# fm_mod_fpga.net
KiCad netlist of a schematic drawn in EAGLE
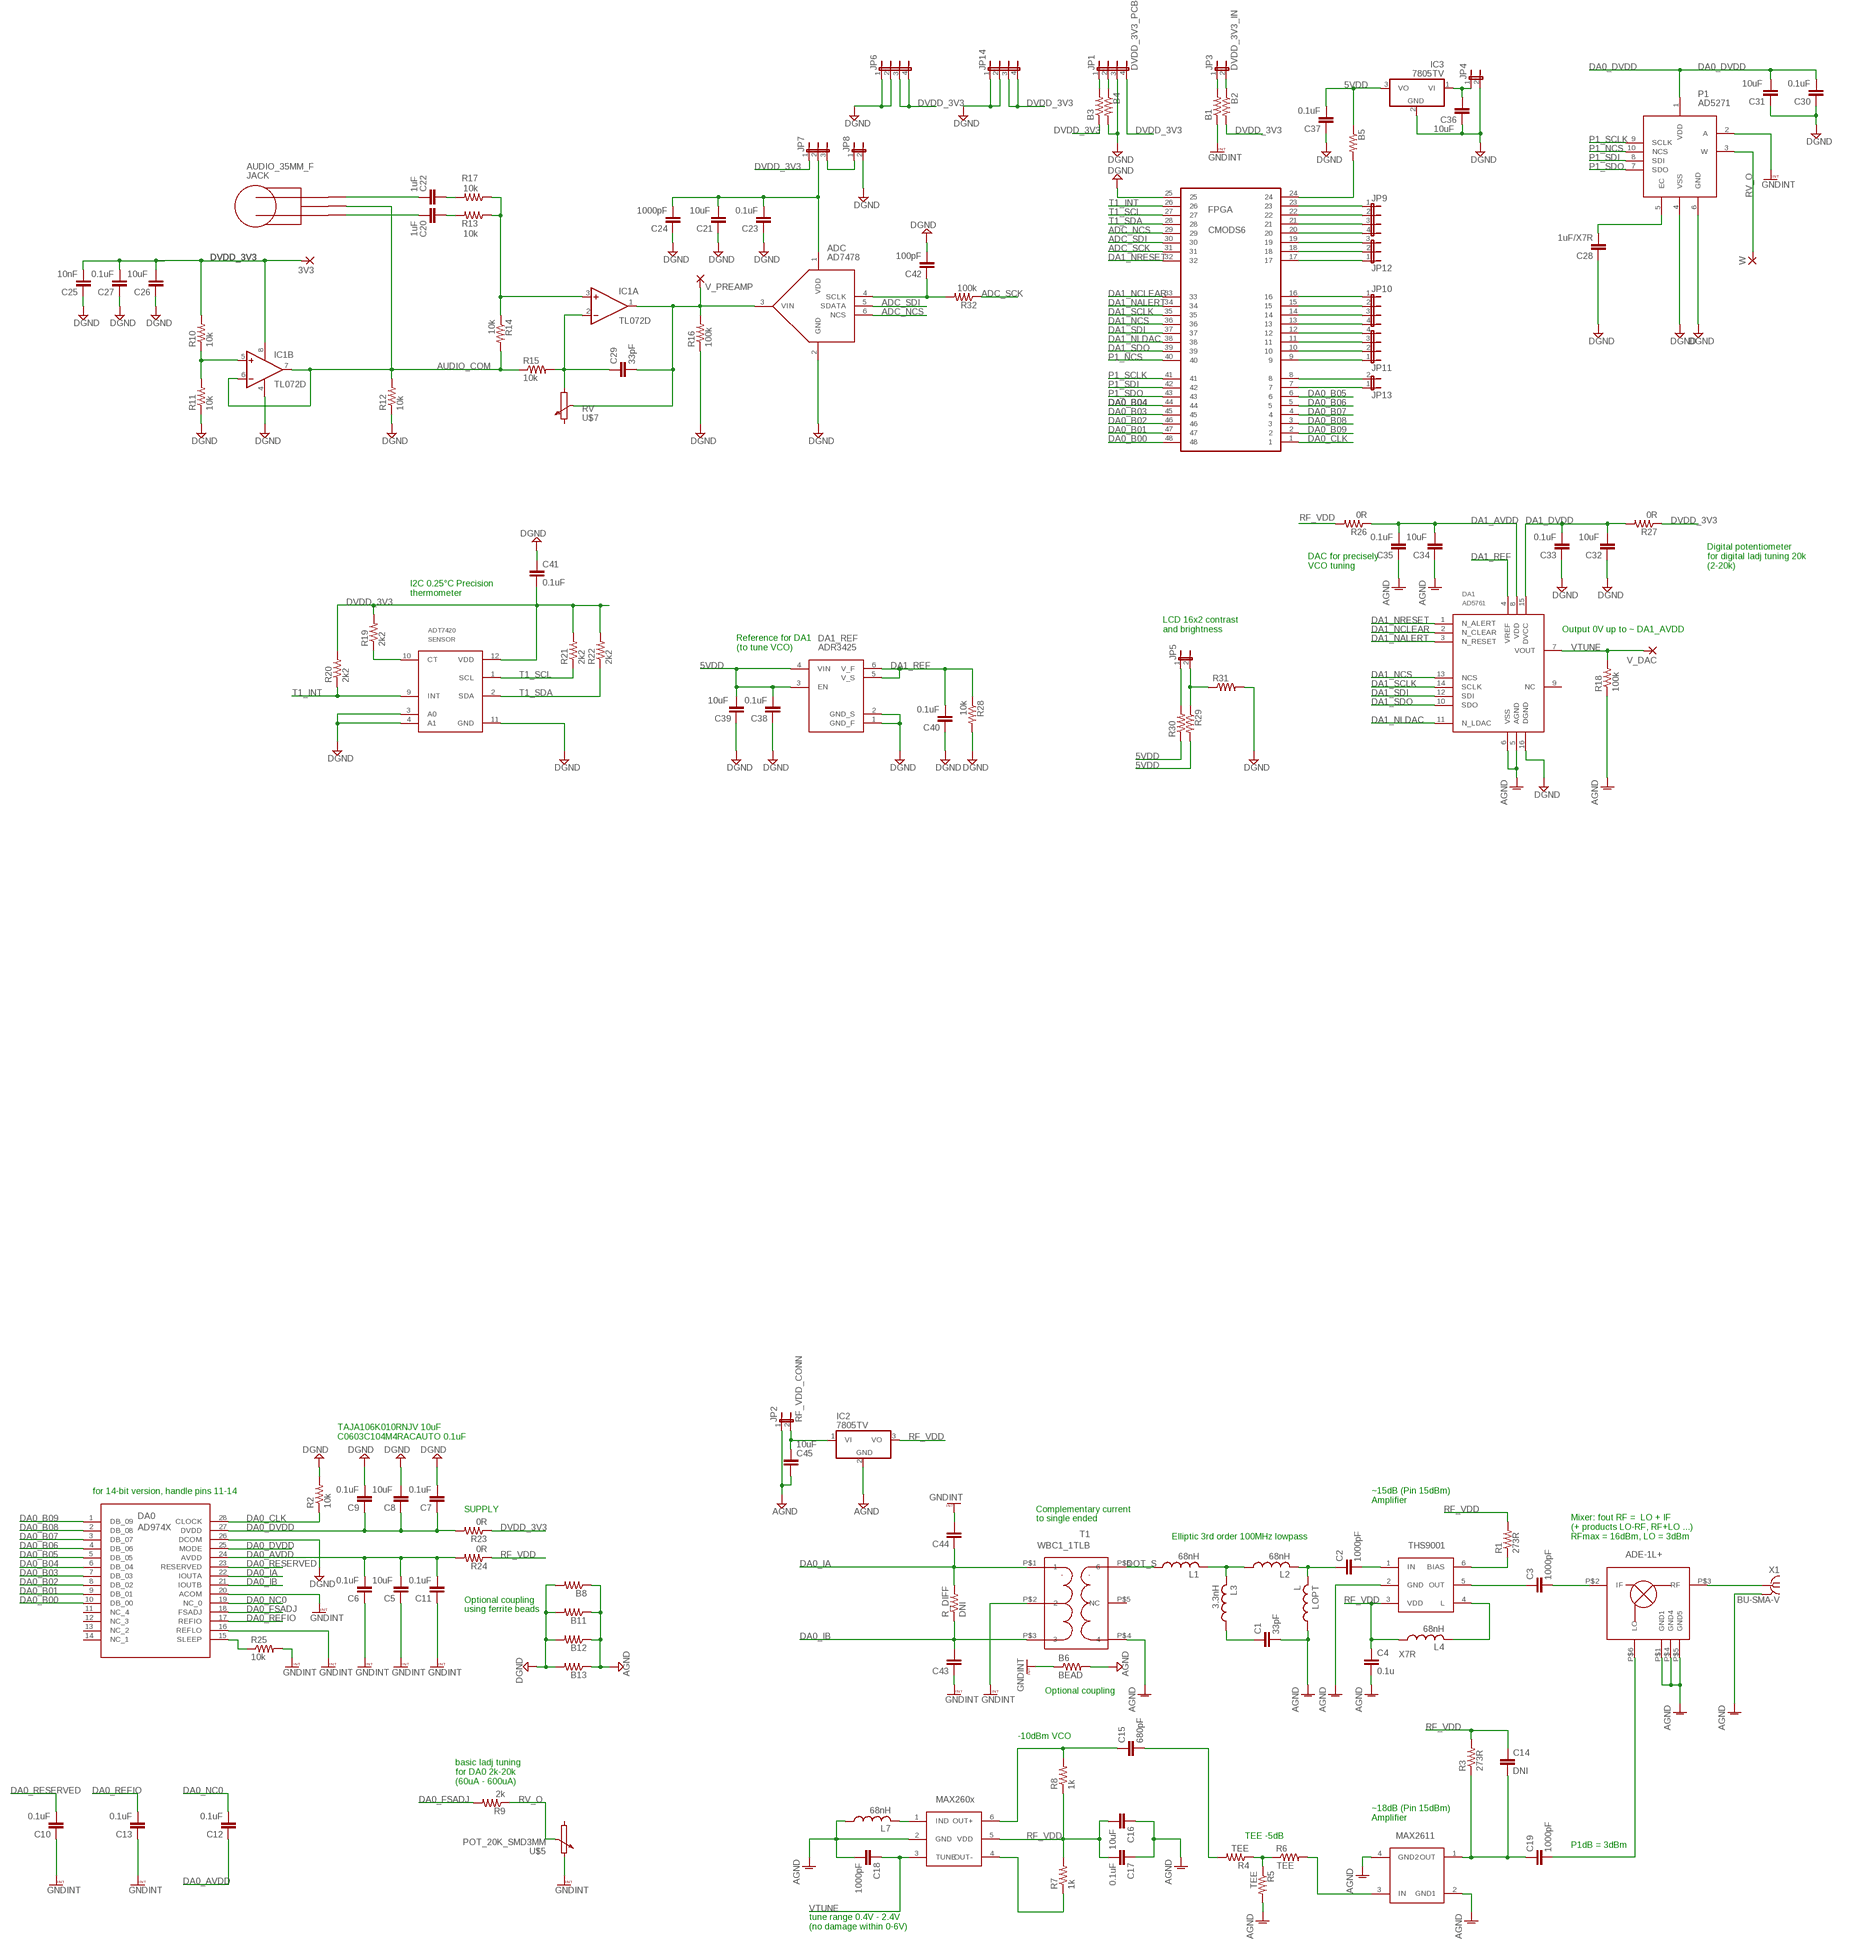
[diagram p0: schematic, sheet 1]

(export (version "E")
  (design (tool "Eeschema 10.0.6"))
  (components
    (comp (ref "3V3")
      (value "WIREPAD1,6/0,8")
      (footprint "eagle-import:1,6_0,8")
      (libsource (lib "eagle-import") (part "WIREPAD1,6/0,8"))
    )
    (comp (ref "ADC")
      (value "AD7478")
      (footprint "eagle-import:SOT23-6")
      (libsource (lib "eagle-import") (part "AD7478"))
    )
    (comp (ref "B1")
      (value "R-US_M0805")
      (footprint "eagle-import:M0805")
      (libsource (lib "eagle-import") (part "resistor_R-US_M0805"))
    )
    (comp (ref "B2")
      (value "R-US_M0805")
      (footprint "eagle-import:M0805")
      (libsource (lib "eagle-import") (part "resistor_R-US_M0805"))
    )
    (comp (ref "B3")
      (value "R-US_M0805")
      (footprint "eagle-import:M0805")
      (libsource (lib "eagle-import") (part "resistor_R-US_M0805"))
    )
    (comp (ref "B4")
      (value "R-US_M0805")
      (footprint "eagle-import:M0805")
      (libsource (lib "eagle-import") (part "resistor_R-US_M0805"))
    )
    (comp (ref "B5")
      (value "R-US_M0805")
      (footprint "eagle-import:M0805")
      (libsource (lib "eagle-import") (part "resistor_R-US_M0805"))
    )
    (comp (ref "B6")
      (value "BEAD")
      (footprint "eagle-import:M0805")
      (libsource (lib "eagle-import") (part "resistor_R-US_M0805"))
    )
    (comp (ref "B8")
      (value "R-US_M0805")
      (footprint "eagle-import:M0805")
      (libsource (lib "eagle-import") (part "resistor_R-US_M0805"))
    )
    (comp (ref "B11")
      (value "R-US_M0805")
      (footprint "eagle-import:M0805")
      (libsource (lib "eagle-import") (part "resistor_R-US_M0805"))
    )
    (comp (ref "B12")
      (value "R-US_M0805")
      (footprint "eagle-import:M0805")
      (libsource (lib "eagle-import") (part "resistor_R-US_M0805"))
    )
    (comp (ref "B13")
      (value "R-US_M0805")
      (footprint "eagle-import:M0805")
      (libsource (lib "eagle-import") (part "resistor_R-US_M0805"))
    )
    (comp (ref "C1")
      (value "33pF")
      (footprint "eagle-import:C0603")
      (libsource (lib "eagle-import") (part "C-EUC0603"))
    )
    (comp (ref "C2")
      (value "1000pF")
      (footprint "eagle-import:C0805")
      (libsource (lib "eagle-import") (part "C-EUC0805"))
    )
    (comp (ref "C3")
      (value "1000pF")
      (footprint "eagle-import:C0805")
      (libsource (lib "eagle-import") (part "C-EUC0805"))
    )
    (comp (ref "C4")
      (value "0.1u")
      (footprint "eagle-import:C0805")
      (libsource (lib "eagle-import") (part "C-EUC0805"))
    )
    (comp (ref "C5")
      (value "10uF")
      (footprint "eagle-import:C1206")
      (libsource (lib "eagle-import") (part "C-EUC1206"))
    )
    (comp (ref "C6")
      (value "0.1uF")
      (footprint "eagle-import:C0603")
      (libsource (lib "eagle-import") (part "C-EUC0603"))
    )
    (comp (ref "C7")
      (value "0.1uF")
      (footprint "eagle-import:C0603")
      (libsource (lib "eagle-import") (part "C-EUC0603"))
    )
    (comp (ref "C8")
      (value "10uF")
      (footprint "eagle-import:C1206")
      (libsource (lib "eagle-import") (part "C-EUC1206"))
    )
    (comp (ref "C9")
      (value "0.1uF")
      (footprint "eagle-import:C0603")
      (libsource (lib "eagle-import") (part "C-EUC0603"))
    )
    (comp (ref "C10")
      (value "0.1uF")
      (footprint "eagle-import:C0603")
      (libsource (lib "eagle-import") (part "C-EUC0603"))
    )
    (comp (ref "C11")
      (value "0.1uF")
      (footprint "eagle-import:C0603")
      (libsource (lib "eagle-import") (part "C-EUC0603"))
    )
    (comp (ref "C12")
      (value "0.1uF")
      (footprint "eagle-import:C0603")
      (libsource (lib "eagle-import") (part "C-EUC0603"))
    )
    (comp (ref "C13")
      (value "0.1uF")
      (footprint "eagle-import:C0603")
      (libsource (lib "eagle-import") (part "C-EUC0603"))
    )
    (comp (ref "C14")
      (value "DNI")
      (footprint "eagle-import:C0603")
      (libsource (lib "eagle-import") (part "C-EUC0603"))
    )
    (comp (ref "C15")
      (value "680pF")
      (footprint "eagle-import:C0805")
      (libsource (lib "eagle-import") (part "C-EUC0805"))
    )
    (comp (ref "C16")
      (value "10uF")
      (footprint "eagle-import:C1206")
      (libsource (lib "eagle-import") (part "C-EUC1206"))
    )
    (comp (ref "C17")
      (value "0.1uF")
      (footprint "eagle-import:C0603")
      (libsource (lib "eagle-import") (part "C-EUC0603"))
    )
    (comp (ref "C18")
      (value "1000pF")
      (footprint "eagle-import:C0805")
      (libsource (lib "eagle-import") (part "C-EUC0805"))
    )
    (comp (ref "C19")
      (value "1000pF")
      (footprint "eagle-import:C0805")
      (libsource (lib "eagle-import") (part "C-EUC0805"))
    )
    (comp (ref "C20")
      (value "1uF")
      (footprint "eagle-import:C1206")
      (libsource (lib "eagle-import") (part "C-EUC1206"))
    )
    (comp (ref "C21")
      (value "10uF")
      (footprint "eagle-import:C1206")
      (libsource (lib "eagle-import") (part "C-EUC1206"))
    )
    (comp (ref "C22")
      (value "1uF")
      (footprint "eagle-import:C1206")
      (libsource (lib "eagle-import") (part "C-EUC1206"))
    )
    (comp (ref "C23")
      (value "0.1uF")
      (footprint "eagle-import:C0603")
      (libsource (lib "eagle-import") (part "C-EUC0603"))
    )
    (comp (ref "C24")
      (value "1000pF")
      (footprint "eagle-import:C0805")
      (libsource (lib "eagle-import") (part "C-EUC0805"))
    )
    (comp (ref "C25")
      (value "10nF")
      (footprint "eagle-import:C0805")
      (libsource (lib "eagle-import") (part "C-EUC0805"))
    )
    (comp (ref "C26")
      (value "10uF")
      (footprint "eagle-import:C1206")
      (libsource (lib "eagle-import") (part "C-EUC1206"))
    )
    (comp (ref "C27")
      (value "0.1uF")
      (footprint "eagle-import:C0603")
      (libsource (lib "eagle-import") (part "C-EUC0603"))
    )
    (comp (ref "C28")
      (value "1uF/X7R")
      (footprint "eagle-import:C0805")
      (libsource (lib "eagle-import") (part "C-EUC0805"))
    )
    (comp (ref "C29")
      (value "33pF")
      (footprint "eagle-import:C0603")
      (libsource (lib "eagle-import") (part "C-EUC0603"))
    )
    (comp (ref "C30")
      (value "0.1uF")
      (footprint "eagle-import:C0603")
      (libsource (lib "eagle-import") (part "C-EUC0603"))
    )
    (comp (ref "C31")
      (value "10uF")
      (footprint "eagle-import:C1206")
      (libsource (lib "eagle-import") (part "C-EUC1206"))
    )
    (comp (ref "C32")
      (value "10uF")
      (footprint "eagle-import:C1206")
      (libsource (lib "eagle-import") (part "C-EUC1206"))
    )
    (comp (ref "C33")
      (value "0.1uF")
      (footprint "eagle-import:C0603")
      (libsource (lib "eagle-import") (part "C-EUC0603"))
    )
    (comp (ref "C34")
      (value "10uF")
      (footprint "eagle-import:C1206")
      (libsource (lib "eagle-import") (part "C-EUC1206"))
    )
    (comp (ref "C35")
      (value "0.1uF")
      (footprint "eagle-import:C0603")
      (libsource (lib "eagle-import") (part "C-EUC0603"))
    )
    (comp (ref "C36")
      (value "10uF")
      (footprint "eagle-import:C1206")
      (libsource (lib "eagle-import") (part "C-EUC1206"))
    )
    (comp (ref "C37")
      (value "0.1uF")
      (footprint "eagle-import:C0603")
      (libsource (lib "eagle-import") (part "C-EUC0603"))
    )
    (comp (ref "C38")
      (value "0.1uF")
      (footprint "eagle-import:C0603")
      (libsource (lib "eagle-import") (part "C-EUC0603"))
    )
    (comp (ref "C39")
      (value "10uF")
      (footprint "eagle-import:C1206")
      (libsource (lib "eagle-import") (part "C-EUC1206"))
    )
    (comp (ref "C40")
      (value "0.1uF")
      (footprint "eagle-import:C0603")
      (libsource (lib "eagle-import") (part "C-EUC0603"))
    )
    (comp (ref "C41")
      (value "0.1uF")
      (footprint "eagle-import:C0603")
      (libsource (lib "eagle-import") (part "C-EUC0603"))
    )
    (comp (ref "C42")
      (value "100pF")
      (footprint "eagle-import:C0603")
      (libsource (lib "eagle-import") (part "C-EUC0603"))
    )
    (comp (ref "C43")
      (value "C-EUC0402")
      (footprint "eagle-import:C0402")
      (libsource (lib "eagle-import") (part "C-EUC0402"))
    )
    (comp (ref "C44")
      (value "C-EUC0402")
      (footprint "eagle-import:C0402")
      (libsource (lib "eagle-import") (part "C-EUC0402"))
    )
    (comp (ref "C45")
      (value "10uF")
      (footprint "eagle-import:C1206")
      (libsource (lib "eagle-import") (part "C-EUC1206"))
    )
    (comp (ref "DA0")
      (value "AD974X")
      (footprint "eagle-import:TSSOP28")
      (libsource (lib "eagle-import") (part "AD974X"))
    )
    (comp (ref "DA1")
      (value "AD5761")
      (footprint "eagle-import:TSSOP-16")
      (libsource (lib "eagle-import") (part "AD5761"))
    )
    (comp (ref "DA1_REF")
      (value "ADR3425")
      (footprint "eagle-import:SOT23-6")
      (libsource (lib "eagle-import") (part "ADR3425"))
    )
    (comp (ref "FPGA")
      (value "CMODS6")
      (footprint "eagle-import:CMODS6_DIP48")
      (libsource (lib "eagle-import") (part "CMODS6"))
    )
    (comp (ref "IC1")
      (value "TL072D")
      (footprint "eagle-import:SO08")
      (libsource (lib "eagle-import") (part "TL072D"))
    )
    (comp (ref "IC2")
      (value "7805TV")
      (footprint "eagle-import:TO220V")
      (libsource (lib "eagle-import") (part "78TV05"))
    )
    (comp (ref "IC3")
      (value "7805TV")
      (footprint "eagle-import:TO220V")
      (libsource (lib "eagle-import") (part "78TV05"))
    )
    (comp (ref "JACK")
      (value "AUDIO_35MM_F")
      (footprint "eagle-import:AUDIO_35MM_F")
      (libsource (lib "eagle-import") (part "AUDIO_35MM_F"))
    )
    (comp (ref "JP1")
      (value "DVDD_3V3_PCB")
      (footprint "eagle-import:JP4")
      (libsource (lib "eagle-import") (part "JP4E"))
    )
    (comp (ref "JP2")
      (value "RF_VDD_CONN")
      (footprint "eagle-import:JP1")
      (libsource (lib "eagle-import") (part "JP1E"))
    )
    (comp (ref "JP3")
      (value "DVDD_3V3_IN")
      (footprint "eagle-import:JP1")
      (libsource (lib "eagle-import") (part "JP1E"))
    )
    (comp (ref "JP4")
      (value "JP1E")
      (footprint "eagle-import:JP1")
      (libsource (lib "eagle-import") (part "JP1E"))
    )
    (comp (ref "JP5")
      (value "JP1E")
      (footprint "eagle-import:JP1")
      (libsource (lib "eagle-import") (part "JP1E"))
    )
    (comp (ref "JP6")
      (value "JP4E")
      (footprint "eagle-import:JP4")
      (libsource (lib "eagle-import") (part "JP4E"))
    )
    (comp (ref "JP7")
      (value "JP2E")
      (footprint "eagle-import:JP2")
      (libsource (lib "eagle-import") (part "JP2E"))
    )
    (comp (ref "JP8")
      (value "JP1E")
      (footprint "eagle-import:JP1")
      (libsource (lib "eagle-import") (part "JP1E"))
    )
    (comp (ref "JP9")
      (value "JP4E")
      (footprint "eagle-import:JP4")
      (libsource (lib "eagle-import") (part "JP4E"))
    )
    (comp (ref "JP10")
      (value "JP4E")
      (footprint "eagle-import:JP4")
      (libsource (lib "eagle-import") (part "JP4E"))
    )
    (comp (ref "JP11")
      (value "JP4E")
      (footprint "eagle-import:JP4")
      (libsource (lib "eagle-import") (part "JP4E"))
    )
    (comp (ref "JP12")
      (value "JP2E")
      (footprint "eagle-import:JP2")
      (libsource (lib "eagle-import") (part "JP2E"))
    )
    (comp (ref "JP13")
      (value "JP1E")
      (footprint "eagle-import:JP1")
      (libsource (lib "eagle-import") (part "JP1E"))
    )
    (comp (ref "JP14")
      (value "JP4E")
      (footprint "eagle-import:JP4")
      (libsource (lib "eagle-import") (part "JP4E"))
    )
    (comp (ref "L1")
      (value "68nH")
      (footprint "eagle-import:COILCRAFT_0805HP")
      (libsource (lib "eagle-import") (part "L"))
    )
    (comp (ref "L2")
      (value "68nH")
      (footprint "eagle-import:COILCRAFT_0805HP")
      (libsource (lib "eagle-import") (part "L"))
    )
    (comp (ref "L3")
      (value "3.3nH")
      (footprint "eagle-import:COILCRAFT_0805HP")
      (libsource (lib "eagle-import") (part "L"))
    )
    (comp (ref "L4")
      (value "68nH")
      (footprint "eagle-import:COILCRAFT_0805HP")
      (libsource (lib "eagle-import") (part "L"))
    )
    (comp (ref "L7")
      (value "68nH")
      (footprint "eagle-import:COILCRAFT_0805HP")
      (libsource (lib "eagle-import") (part "L"))
    )
    (comp (ref "LOPT")
      (value "L")
      (footprint "eagle-import:COILCRAFT_0805HP")
      (libsource (lib "eagle-import") (part "L"))
    )
    (comp (ref "P1")
      (value "AD5271")
      (footprint "eagle-import:MSOP-10")
      (libsource (lib "eagle-import") (part "AD5271"))
    )
    (comp (ref "R1")
      (value "273R")
      (footprint "eagle-import:R0805")
      (libsource (lib "eagle-import") (part "resistor_R-US_R0805"))
    )
    (comp (ref "R2")
      (value "10k")
      (footprint "eagle-import:R0805")
      (libsource (lib "eagle-import") (part "resistor_R-US_R0805"))
    )
    (comp (ref "R3")
      (value "273R")
      (footprint "eagle-import:R0805")
      (libsource (lib "eagle-import") (part "resistor_R-US_R0805"))
    )
    (comp (ref "R4")
      (value "TEE")
      (footprint "eagle-import:R0805")
      (libsource (lib "eagle-import") (part "resistor_R-US_R0805"))
    )
    (comp (ref "R5")
      (value "TEE")
      (footprint "eagle-import:R0805")
      (libsource (lib "eagle-import") (part "resistor_R-US_R0805"))
    )
    (comp (ref "R6")
      (value "TEE")
      (footprint "eagle-import:R0805")
      (libsource (lib "eagle-import") (part "resistor_R-US_R0805"))
    )
    (comp (ref "R7")
      (value "1k")
      (footprint "eagle-import:R0805")
      (libsource (lib "eagle-import") (part "resistor_R-US_R0805"))
    )
    (comp (ref "R8")
      (value "1k")
      (footprint "eagle-import:R0805")
      (libsource (lib "eagle-import") (part "resistor_R-US_R0805"))
    )
    (comp (ref "R9")
      (value "2k")
      (footprint "eagle-import:R0805")
      (libsource (lib "eagle-import") (part "resistor_R-US_R0805"))
    )
    (comp (ref "R10")
      (value "10k")
      (footprint "eagle-import:R0805")
      (libsource (lib "eagle-import") (part "resistor_R-US_R0805"))
    )
    (comp (ref "R11")
      (value "10k")
      (footprint "eagle-import:R0805")
      (libsource (lib "eagle-import") (part "resistor_R-US_R0805"))
    )
    (comp (ref "R12")
      (value "10k")
      (footprint "eagle-import:R0805")
      (libsource (lib "eagle-import") (part "resistor_R-US_R0805"))
    )
    (comp (ref "R13")
      (value "10k")
      (footprint "eagle-import:R0805")
      (libsource (lib "eagle-import") (part "resistor_R-US_R0805"))
    )
    (comp (ref "R14")
      (value "10k")
      (footprint "eagle-import:R0805")
      (libsource (lib "eagle-import") (part "resistor_R-US_R0805"))
    )
    (comp (ref "R15")
      (value "10k")
      (footprint "eagle-import:R0805")
      (libsource (lib "eagle-import") (part "resistor_R-US_R0805"))
    )
    (comp (ref "R16")
      (value "100k")
      (footprint "eagle-import:R0805")
      (libsource (lib "eagle-import") (part "resistor_R-US_R0805"))
    )
    (comp (ref "R17")
      (value "10k")
      (footprint "eagle-import:R0805")
      (libsource (lib "eagle-import") (part "resistor_R-US_R0805"))
    )
    (comp (ref "R18")
      (value "100k")
      (footprint "eagle-import:R0805")
      (libsource (lib "eagle-import") (part "resistor_R-US_R0805"))
    )
    (comp (ref "R19")
      (value "2k2")
      (footprint "eagle-import:R0805")
      (libsource (lib "eagle-import") (part "resistor_R-US_R0805"))
    )
    (comp (ref "R20")
      (value "2k2")
      (footprint "eagle-import:R0805")
      (libsource (lib "eagle-import") (part "resistor_R-US_R0805"))
    )
    (comp (ref "R21")
      (value "2k2")
      (footprint "eagle-import:R0805")
      (libsource (lib "eagle-import") (part "resistor_R-US_R0805"))
    )
    (comp (ref "R22")
      (value "2k2")
      (footprint "eagle-import:R0805")
      (libsource (lib "eagle-import") (part "resistor_R-US_R0805"))
    )
    (comp (ref "R23")
      (value "0R")
      (footprint "eagle-import:R0805")
      (libsource (lib "eagle-import") (part "resistor_R-US_R0805"))
    )
    (comp (ref "R24")
      (value "0R")
      (footprint "eagle-import:R0805")
      (libsource (lib "eagle-import") (part "resistor_R-US_R0805"))
    )
    (comp (ref "R25")
      (value "10k")
      (footprint "eagle-import:R0805")
      (libsource (lib "eagle-import") (part "resistor_R-US_R0805"))
    )
    (comp (ref "R26")
      (value "0R")
      (footprint "eagle-import:R0805")
      (libsource (lib "eagle-import") (part "resistor_R-US_R0805"))
    )
    (comp (ref "R27")
      (value "0R")
      (footprint "eagle-import:R0805")
      (libsource (lib "eagle-import") (part "resistor_R-US_R0805"))
    )
    (comp (ref "R28")
      (value "10k")
      (footprint "eagle-import:R0805")
      (libsource (lib "eagle-import") (part "resistor_R-US_R0805"))
    )
    (comp (ref "R29")
      (value "R-US_R0805")
      (footprint "eagle-import:R0805")
      (libsource (lib "eagle-import") (part "resistor_R-US_R0805"))
    )
    (comp (ref "R30")
      (value "R-US_R0805")
      (footprint "eagle-import:R0805")
      (libsource (lib "eagle-import") (part "resistor_R-US_R0805"))
    )
    (comp (ref "R31")
      (value "R-US_R0805")
      (footprint "eagle-import:R0805")
      (libsource (lib "eagle-import") (part "resistor_R-US_R0805"))
    )
    (comp (ref "R32")
      (value "100k")
      (footprint "eagle-import:R0805")
      (libsource (lib "eagle-import") (part "resistor_R-US_R0805"))
    )
    (comp (ref "R_DIFF")
      (value "DNI")
      (footprint "eagle-import:R0603")
      (libsource (lib "eagle-import") (part "R-US_R0603"))
    )
    (comp (ref "SENSOR")
      (value "ADT7420")
      (footprint "eagle-import:LFCSP-16")
      (libsource (lib "eagle-import") (part "ADT7420"))
    )
    (comp (ref "T1")
      (value "WBC1_1TLB")
      (footprint "eagle-import:WBC1_1")
      (libsource (lib "eagle-import") (part "WBC1_1TLB"))
    )
    (comp (ref "U$2")
      (value "THS9001")
      (footprint "eagle-import:SOT23-6")
      (libsource (lib "eagle-import") (part "THS9001"))
    )
    (comp (ref "U$3")
      (value "MAX2611")
      (footprint "eagle-import:SOT143-4")
      (libsource (lib "eagle-import") (part "MAX2611"))
    )
    (comp (ref "U$4")
      (value "MAX260X")
      (footprint "eagle-import:SOT23-6")
      (libsource (lib "eagle-import") (part "MAX260X"))
    )
    (comp (ref "U$5")
      (value "POT_20K_SMD3MM")
      (footprint "eagle-import:POT_3MM_SMD")
      (libsource (lib "eagle-import") (part "POT_20K_SMD3MM"))
    )
    (comp (ref "U$6")
      (value "ADE-1L+")
      (footprint "eagle-import:ADE-1L+")
      (libsource (lib "eagle-import") (part "ADE-1L+"))
    )
    (comp (ref "U$7") (value "RV") (footprint "eagle-import:RV") (libsource (lib "eagle-import") (part "RV")))
    (comp (ref "V_DAC")
      (value "WIREPAD1,6/0,8")
      (footprint "eagle-import:1,6_0,8")
      (libsource (lib "eagle-import") (part "WIREPAD1,6/0,8"))
    )
    (comp (ref "V_PREAMP")
      (value "WIREPAD1,6/0,8")
      (footprint "eagle-import:1,6_0,8")
      (libsource (lib "eagle-import") (part "WIREPAD1,6/0,8"))
    )
    (comp (ref "W")
      (value "WIREPAD1,6/0,8")
      (footprint "eagle-import:1,6_0,8")
      (libsource (lib "eagle-import") (part "WIREPAD1,6/0,8"))
    )
    (comp (ref "X1")
      (value "BU-SMA-V")
      (footprint "eagle-import:BU-SMA-V")
      (libsource (lib "eagle-import") (part "BU-SMA-V"))
    )
  )
  (nets
    (net (code "1") (name "/5VDD") (class "Default")
      (node (ref "B5") (pin "1") (pinfunction "1_1") (pintype "passive"))
      (node (ref "C37") (pin "2") (pinfunction "2_2") (pintype "passive"))
      (node (ref "C38") (pin "2") (pinfunction "2_2") (pintype "passive"))
      (node (ref "C39") (pin "2") (pinfunction "2_2") (pintype "passive"))
      (node (ref "DA1_REF") (pin "3") (pinfunction "EN_3") (pintype "bidirectional"))
      (node (ref "DA1_REF") (pin "4") (pinfunction "VIN_4") (pintype "bidirectional"))
      (node (ref "IC3") (pin "3") (pinfunction "VO_3") (pintype "passive"))
      (node (ref "R29") (pin "2") (pinfunction "2_2") (pintype "passive"))
      (node (ref "R30") (pin "1") (pinfunction "1_1") (pintype "passive"))
    )
    (net (code "2") (name "/ADC_NCS") (class "Default")
      (node (ref "ADC") (pin "6") (pinfunction "NCS_6") (pintype "bidirectional"))
      (node (ref "FPGA") (pin "29") (pinfunction "29_29") (pintype "output"))
    )
    (net (code "3") (name "/ADC_SCK") (class "Default")
      (node (ref "FPGA") (pin "31") (pinfunction "31_31") (pintype "output"))
      (node (ref "R32") (pin "1") (pinfunction "1_1") (pintype "passive"))
    )
    (net (code "4") (name "/ADC_SDI") (class "Default")
      (node (ref "ADC") (pin "5") (pinfunction "SDATA_5") (pintype "bidirectional"))
      (node (ref "FPGA") (pin "30") (pinfunction "30_30") (pintype "output"))
    )
    (net (code "5") (name "/AUDIO_COM") (class "Default")
      (node (ref "IC1") (pin "6") (pinfunction "-IN_6") (pintype "input"))
      (node (ref "IC1") (pin "7") (pinfunction "OUT_7") (pintype "output"))
      (node (ref "JACK") (pin "1") (pinfunction "P$1_1") (pintype "bidirectional"))
      (node (ref "R12") (pin "2") (pinfunction "2_2") (pintype "passive"))
      (node (ref "R14") (pin "2") (pinfunction "2_2") (pintype "passive"))
      (node (ref "R15") (pin "1") (pinfunction "1_1") (pintype "passive"))
    )
    (net (code "6") (name "/DA0_AVDD") (class "Default")
      (node (ref "C11") (pin "2") (pinfunction "2_2") (pintype "passive"))
      (node (ref "C12") (pin "1") (pinfunction "1_1") (pintype "passive"))
      (node (ref "C5") (pin "2") (pinfunction "2_2") (pintype "passive"))
      (node (ref "C6") (pin "2") (pinfunction "2_2") (pintype "passive"))
      (node (ref "DA0") (pin "24") (pinfunction "AVDD_24") (pintype "bidirectional"))
      (node (ref "R24") (pin "2") (pinfunction "2_2") (pintype "passive"))
    )
    (net (code "7") (name "/DA0_B00") (class "Default")
      (node (ref "DA0") (pin "10") (pinfunction "DB_00_10") (pintype "bidirectional"))
      (node (ref "FPGA") (pin "48") (pinfunction "48_48") (pintype "bidirectional"))
    )
    (net (code "8") (name "/DA0_B01") (class "Default")
      (node (ref "DA0") (pin "9") (pinfunction "DB_01_9") (pintype "bidirectional"))
      (node (ref "FPGA") (pin "47") (pinfunction "47_47") (pintype "bidirectional"))
    )
    (net (code "9") (name "/DA0_B02") (class "Default")
      (node (ref "DA0") (pin "8") (pinfunction "DB_02_8") (pintype "bidirectional"))
      (node (ref "FPGA") (pin "46") (pinfunction "46_46") (pintype "bidirectional"))
    )
    (net (code "10") (name "/DA0_B03") (class "Default")
      (node (ref "DA0") (pin "7") (pinfunction "DB_03_7") (pintype "bidirectional"))
      (node (ref "FPGA") (pin "45") (pinfunction "45_45") (pintype "bidirectional"))
    )
    (net (code "11") (name "/DA0_B04") (class "Default")
      (node (ref "DA0") (pin "6") (pinfunction "DB_04_6") (pintype "bidirectional"))
      (node (ref "FPGA") (pin "44") (pinfunction "44_44") (pintype "bidirectional"))
    )
    (net (code "12") (name "/DA0_B05") (class "Default")
      (node (ref "DA0") (pin "5") (pinfunction "DB_05_5") (pintype "bidirectional"))
      (node (ref "FPGA") (pin "6") (pinfunction "6_6") (pintype "bidirectional"))
    )
    (net (code "13") (name "/DA0_B06") (class "Default")
      (node (ref "DA0") (pin "4") (pinfunction "DB_06_4") (pintype "bidirectional"))
      (node (ref "FPGA") (pin "5") (pinfunction "5_5") (pintype "bidirectional"))
    )
    (net (code "14") (name "/DA0_B07") (class "Default")
      (node (ref "DA0") (pin "3") (pinfunction "DB_07_3") (pintype "bidirectional"))
      (node (ref "FPGA") (pin "4") (pinfunction "4_4") (pintype "bidirectional"))
    )
    (net (code "15") (name "/DA0_B08") (class "Default")
      (node (ref "DA0") (pin "2") (pinfunction "DB_08_2") (pintype "bidirectional"))
      (node (ref "FPGA") (pin "3") (pinfunction "3_3") (pintype "bidirectional"))
    )
    (net (code "16") (name "/DA0_B09") (class "Default")
      (node (ref "DA0") (pin "1") (pinfunction "DB_09_1") (pintype "bidirectional"))
      (node (ref "FPGA") (pin "2") (pinfunction "2_2") (pintype "bidirectional"))
    )
    (net (code "17") (name "/DA0_CLK") (class "Default")
      (node (ref "DA0") (pin "28") (pinfunction "CLOCK_28") (pintype "bidirectional"))
      (node (ref "FPGA") (pin "1") (pinfunction "1_1") (pintype "bidirectional"))
      (node (ref "R2") (pin "1") (pinfunction "1_1") (pintype "passive"))
    )
    (net (code "18") (name "/DA0_DVDD") (class "Default")
      (node (ref "C30") (pin "2") (pinfunction "2_2") (pintype "passive"))
      (node (ref "C31") (pin "2") (pinfunction "2_2") (pintype "passive"))
      (node (ref "C7") (pin "1") (pinfunction "1_1") (pintype "passive"))
      (node (ref "C8") (pin "1") (pinfunction "1_1") (pintype "passive"))
      (node (ref "C9") (pin "1") (pinfunction "1_1") (pintype "passive"))
      (node (ref "DA0") (pin "25") (pinfunction "MODE_25") (pintype "bidirectional"))
      (node (ref "DA0") (pin "27") (pinfunction "DVDD_27") (pintype "bidirectional"))
      (node (ref "P1") (pin "1") (pinfunction "VDD_1") (pintype "bidirectional"))
      (node (ref "R23") (pin "2") (pinfunction "2_2") (pintype "passive"))
    )
    (net (code "19") (name "/DA0_FSADJ") (class "Default")
      (node (ref "DA0") (pin "18") (pinfunction "FSADJ_18") (pintype "bidirectional"))
      (node (ref "R9") (pin "2") (pinfunction "2_2") (pintype "passive"))
    )
    (net (code "20") (name "/DA0_IA") (class "Default")
      (node (ref "C44") (pin "1") (pinfunction "1_1") (pintype "passive"))
      (node (ref "DA0") (pin "22") (pinfunction "IOUTA_22") (pintype "bidirectional"))
      (node (ref "R_DIFF") (pin "2") (pinfunction "2_2") (pintype "passive"))
      (node (ref "T1") (pin "P$1") (pinfunction "1_P$1") (pintype "bidirectional"))
    )
    (net (code "21") (name "/DA0_IB") (class "Default")
      (node (ref "C43") (pin "2") (pinfunction "2_2") (pintype "passive"))
      (node (ref "DA0") (pin "21") (pinfunction "IOUTB_21") (pintype "bidirectional"))
      (node (ref "R_DIFF") (pin "1") (pinfunction "1_1") (pintype "passive"))
      (node (ref "T1") (pin "P$3") (pinfunction "3_P$3") (pintype "bidirectional"))
    )
    (net (code "22") (name "/DA0_NC0") (class "Default")
      (node (ref "C12") (pin "2") (pinfunction "2_2") (pintype "passive"))
      (node (ref "DA0") (pin "19") (pinfunction "NC_0_19") (pintype "bidirectional"))
    )
    (net (code "23") (name "/DA0_REFIO") (class "Default")
      (node (ref "C13") (pin "2") (pinfunction "2_2") (pintype "passive"))
      (node (ref "DA0") (pin "17") (pinfunction "REFIO_17") (pintype "bidirectional"))
    )
    (net (code "24") (name "/DA0_RESERVED") (class "Default")
      (node (ref "C10") (pin "2") (pinfunction "2_2") (pintype "passive"))
      (node (ref "DA0") (pin "23") (pinfunction "RESERVED_23") (pintype "bidirectional"))
    )
    (net (code "25") (name "/DA1_AVDD") (class "Default")
      (node (ref "C34") (pin "2") (pinfunction "2_2") (pintype "passive"))
      (node (ref "C35") (pin "2") (pinfunction "2_2") (pintype "passive"))
      (node (ref "DA1") (pin "8") (pinfunction "VDD_8") (pintype "bidirectional"))
      (node (ref "R26") (pin "1") (pinfunction "1_1") (pintype "passive"))
    )
    (net (code "26") (name "/DA1_DVDD") (class "Default")
      (node (ref "C32") (pin "2") (pinfunction "2_2") (pintype "passive"))
      (node (ref "C33") (pin "2") (pinfunction "2_2") (pintype "passive"))
      (node (ref "DA1") (pin "15") (pinfunction "DVCC_15") (pintype "bidirectional"))
      (node (ref "R27") (pin "2") (pinfunction "2_2") (pintype "passive"))
    )
    (net (code "27") (name "/DA1_NALERT") (class "Default")
      (node (ref "DA1") (pin "3") (pinfunction "N_RESET_3") (pintype "bidirectional"))
      (node (ref "FPGA") (pin "34") (pinfunction "34_34") (pintype "output"))
    )
    (net (code "28") (name "/DA1_NCLEAR") (class "Default")
      (node (ref "DA1") (pin "2") (pinfunction "N_CLEAR_2") (pintype "bidirectional"))
      (node (ref "FPGA") (pin "33") (pinfunction "33_33") (pintype "output"))
    )
    (net (code "29") (name "/DA1_NCS") (class "Default")
      (node (ref "DA1") (pin "13") (pinfunction "NCS_13") (pintype "bidirectional"))
      (node (ref "FPGA") (pin "36") (pinfunction "36_36") (pintype "output"))
    )
    (net (code "30") (name "/DA1_NLDAC") (class "Default")
      (node (ref "DA1") (pin "11") (pinfunction "N_LDAC_11") (pintype "bidirectional"))
      (node (ref "FPGA") (pin "38") (pinfunction "38_38") (pintype "output"))
    )
    (net (code "31") (name "/DA1_NRESET") (class "Default")
      (node (ref "DA1") (pin "1") (pinfunction "N_ALERT_1") (pintype "bidirectional"))
      (node (ref "FPGA") (pin "32") (pinfunction "32_32") (pintype "output"))
    )
    (net (code "32") (name "/DA1_REF") (class "Default")
      (node (ref "C40") (pin "2") (pinfunction "2_2") (pintype "passive"))
      (node (ref "DA1") (pin "4") (pinfunction "VREF_4") (pintype "bidirectional"))
      (node (ref "DA1_REF") (pin "5") (pinfunction "V_S_5") (pintype "bidirectional"))
      (node (ref "DA1_REF") (pin "6") (pinfunction "V_F_6") (pintype "bidirectional"))
      (node (ref "R28") (pin "1") (pinfunction "1_1") (pintype "passive"))
    )
    (net (code "33") (name "/DA1_SCLK") (class "Default")
      (node (ref "DA1") (pin "14") (pinfunction "SCLK_14") (pintype "bidirectional"))
      (node (ref "FPGA") (pin "35") (pinfunction "35_35") (pintype "output"))
    )
    (net (code "34") (name "/DA1_SDI") (class "Default")
      (node (ref "DA1") (pin "12") (pinfunction "SDI_12") (pintype "bidirectional"))
      (node (ref "FPGA") (pin "37") (pinfunction "37_37") (pintype "output"))
    )
    (net (code "35") (name "/DA1_SDO") (class "Default")
      (node (ref "DA1") (pin "10") (pinfunction "SDO_10") (pintype "bidirectional"))
      (node (ref "FPGA") (pin "39") (pinfunction "39_39") (pintype "output"))
    )
    (net (code "36") (name "/DOT_S") (class "Default")
      (node (ref "L1") (pin "1") (pinfunction "1_1") (pintype "passive"))
      (node (ref "T1") (pin "P$6") (pinfunction "6_P$6") (pintype "bidirectional"))
    )
    (net (code "37") (name "/DVDD_3V3") (class "Default")
      (node (ref "3V3") (pin "1") (pinfunction "P_1") (pintype "passive"))
      (node (ref "B2") (pin "2") (pinfunction "2_2") (pintype "passive"))
      (node (ref "B3") (pin "1") (pinfunction "1_1") (pintype "passive"))
      (node (ref "C25") (pin "2") (pinfunction "2_2") (pintype "passive"))
      (node (ref "C26") (pin "2") (pinfunction "2_2") (pintype "passive"))
      (node (ref "C27") (pin "2") (pinfunction "2_2") (pintype "passive"))
      (node (ref "C41") (pin "2") (pinfunction "2_2") (pintype "passive"))
      (node (ref "IC1") (pin "8") (pinfunction "V+_8") (pintype "power_in"))
      (node (ref "JP1") (pin "4") (pinfunction "4_4") (pintype "passive"))
      (node (ref "JP14") (pin "3") (pinfunction "3_3") (pintype "passive"))
      (node (ref "JP14") (pin "4") (pinfunction "4_4") (pintype "passive"))
      (node (ref "JP6") (pin "3") (pinfunction "3_3") (pintype "passive"))
      (node (ref "JP6") (pin "4") (pinfunction "4_4") (pintype "passive"))
      (node (ref "JP7") (pin "1") (pinfunction "1_1") (pintype "passive"))
      (node (ref "R10") (pin "2") (pinfunction "2_2") (pintype "passive"))
      (node (ref "R19") (pin "2") (pinfunction "2_2") (pintype "passive"))
      (node (ref "R20") (pin "2") (pinfunction "2_2") (pintype "passive"))
      (node (ref "R21") (pin "2") (pinfunction "2_2") (pintype "passive"))
      (node (ref "R22") (pin "2") (pinfunction "2_2") (pintype "passive"))
      (node (ref "R23") (pin "1") (pinfunction "1_1") (pintype "passive"))
      (node (ref "R27") (pin "1") (pinfunction "1_1") (pintype "passive"))
      (node (ref "SENSOR") (pin "12") (pinfunction "VDD_12") (pintype "bidirectional"))
    )
    (net (code "38") (name "/P1_NCS") (class "Default")
      (node (ref "FPGA") (pin "40") (pinfunction "40_40") (pintype "output"))
      (node (ref "P1") (pin "10") (pinfunction "NCS_10") (pintype "bidirectional"))
    )
    (net (code "39") (name "/P1_SCLK") (class "Default")
      (node (ref "FPGA") (pin "41") (pinfunction "41_41") (pintype "bidirectional"))
      (node (ref "P1") (pin "9") (pinfunction "SCLK_9") (pintype "bidirectional"))
    )
    (net (code "40") (name "/P1_SDI") (class "Default")
      (node (ref "FPGA") (pin "42") (pinfunction "42_42") (pintype "bidirectional"))
      (node (ref "P1") (pin "8") (pinfunction "SDI_8") (pintype "bidirectional"))
    )
    (net (code "41") (name "/P1_SDO") (class "Default")
      (node (ref "FPGA") (pin "43") (pinfunction "43_43") (pintype "bidirectional"))
      (node (ref "P1") (pin "7") (pinfunction "SDO_7") (pintype "bidirectional"))
    )
    (net (code "42") (name "/RF_VDD") (class "Default")
      (node (ref "C14") (pin "1") (pinfunction "1_1") (pintype "passive"))
      (node (ref "C16") (pin "2") (pinfunction "2_2") (pintype "passive"))
      (node (ref "C17") (pin "2") (pinfunction "2_2") (pintype "passive"))
      (node (ref "C4") (pin "1") (pinfunction "1_1") (pintype "passive"))
      (node (ref "IC2") (pin "3") (pinfunction "VO_3") (pintype "passive"))
      (node (ref "L4") (pin "1") (pinfunction "1_1") (pintype "passive"))
      (node (ref "R1") (pin "2") (pinfunction "2_2") (pintype "passive"))
      (node (ref "R24") (pin "1") (pinfunction "1_1") (pintype "passive"))
      (node (ref "R26") (pin "2") (pinfunction "2_2") (pintype "passive"))
      (node (ref "R3") (pin "2") (pinfunction "2_2") (pintype "passive"))
      (node (ref "R7") (pin "2") (pinfunction "2_2") (pintype "passive"))
      (node (ref "R8") (pin "1") (pinfunction "1_1") (pintype "passive"))
      (node (ref "U$2") (pin "3") (pinfunction "VDD_3") (pintype "bidirectional"))
      (node (ref "U$4") (pin "5") (pinfunction "VDD_5") (pintype "bidirectional"))
    )
    (net (code "43") (name "/RV_O") (class "Default")
      (node (ref "P1") (pin "3") (pinfunction "W_3") (pintype "bidirectional"))
      (node (ref "R9") (pin "1") (pinfunction "1_1") (pintype "passive"))
      (node (ref "U$5") (pin "2") (pinfunction "P$2_2") (pintype "bidirectional"))
      (node (ref "W") (pin "1") (pinfunction "P_1") (pintype "passive"))
    )
    (net (code "44") (name "/T1_INT") (class "Default")
      (node (ref "FPGA") (pin "26") (pinfunction "26_26") (pintype "output"))
      (node (ref "R20") (pin "1") (pinfunction "1_1") (pintype "passive"))
      (node (ref "SENSOR") (pin "9") (pinfunction "INT_9") (pintype "bidirectional"))
    )
    (net (code "45") (name "/T1_SCL") (class "Default")
      (node (ref "FPGA") (pin "27") (pinfunction "27_27") (pintype "output"))
      (node (ref "R21") (pin "1") (pinfunction "1_1") (pintype "passive"))
      (node (ref "SENSOR") (pin "1") (pinfunction "SCL_1") (pintype "bidirectional"))
    )
    (net (code "46") (name "/T1_SDA") (class "Default")
      (node (ref "FPGA") (pin "28") (pinfunction "28_28") (pintype "output"))
      (node (ref "R22") (pin "1") (pinfunction "1_1") (pintype "passive"))
      (node (ref "SENSOR") (pin "2") (pinfunction "SDA_2") (pintype "bidirectional"))
    )
    (net (code "47") (name "/VTUNE") (class "Default")
      (node (ref "C18") (pin "1") (pinfunction "1_1") (pintype "passive"))
      (node (ref "DA1") (pin "7") (pinfunction "VOUT_7") (pintype "bidirectional"))
      (node (ref "R18") (pin "2") (pinfunction "2_2") (pintype "passive"))
      (node (ref "U$4") (pin "3") (pinfunction "TUNE_3") (pintype "bidirectional"))
      (node (ref "V_DAC") (pin "1") (pinfunction "P_1") (pintype "passive"))
    )
    (net (code "48") (name "AGND") (class "Default")
      (node (ref "B11") (pin "1") (pinfunction "1_1") (pintype "passive"))
      (node (ref "B12") (pin "1") (pinfunction "1_1") (pintype "passive"))
      (node (ref "B13") (pin "1") (pinfunction "1_1") (pintype "passive"))
      (node (ref "B6") (pin "2") (pinfunction "2_2") (pintype "passive"))
      (node (ref "B8") (pin "1") (pinfunction "1_1") (pintype "passive"))
      (node (ref "C1") (pin "2") (pinfunction "2_2") (pintype "passive"))
      (node (ref "C16") (pin "1") (pinfunction "1_1") (pintype "passive"))
      (node (ref "C17") (pin "1") (pinfunction "1_1") (pintype "passive"))
      (node (ref "C18") (pin "2") (pinfunction "2_2") (pintype "passive"))
      (node (ref "C34") (pin "1") (pinfunction "1_1") (pintype "passive"))
      (node (ref "C35") (pin "1") (pinfunction "1_1") (pintype "passive"))
      (node (ref "C4") (pin "2") (pinfunction "2_2") (pintype "passive"))
      (node (ref "C45") (pin "2") (pinfunction "2_2") (pintype "passive"))
      (node (ref "DA1") (pin "5") (pinfunction "AGND_5") (pintype "bidirectional"))
      (node (ref "DA1") (pin "6") (pinfunction "VSS_6") (pintype "bidirectional"))
      (node (ref "IC2") (pin "2") (pinfunction "GND_2") (pintype "passive"))
      (node (ref "JP2") (pin "1") (pinfunction "1_1") (pintype "passive"))
      (node (ref "L7") (pin "1") (pinfunction "1_1") (pintype "passive"))
      (node (ref "LOPT") (pin "1") (pinfunction "1_1") (pintype "passive"))
      (node (ref "R18") (pin "1") (pinfunction "1_1") (pintype "passive"))
      (node (ref "R5") (pin "2") (pinfunction "2_2") (pintype "passive"))
      (node (ref "T1") (pin "P$4") (pinfunction "4_P$4") (pintype "bidirectional"))
      (node (ref "U$2") (pin "2") (pinfunction "GND_2") (pintype "bidirectional"))
      (node (ref "U$3") (pin "2") (pinfunction "GND1_2") (pintype "bidirectional"))
      (node (ref "U$3") (pin "4") (pinfunction "GND2_4") (pintype "bidirectional"))
      (node (ref "U$4") (pin "2") (pinfunction "GND_2") (pintype "bidirectional"))
      (node (ref "U$6") (pin "P$1") (pinfunction "GND1_P$1") (pintype "bidirectional"))
      (node (ref "U$6") (pin "P$4") (pinfunction "GND4_P$4") (pintype "bidirectional"))
      (node (ref "U$6") (pin "P$5") (pinfunction "GND5_P$5") (pintype "bidirectional"))
      (node (ref "X1") (pin "2") (pinfunction "2_2") (pintype "passive"))
      (node (ref "X1") (pin "3") (pinfunction "2_3") (pintype "passive"))
      (node (ref "X1") (pin "4") (pinfunction "2_4") (pintype "passive"))
      (node (ref "X1") (pin "5") (pinfunction "2_5") (pintype "passive"))
    )
    (net (code "49") (name "DGND") (class "Default")
      (node (ref "ADC") (pin "2") (pinfunction "GND_2") (pintype "bidirectional"))
      (node (ref "B11") (pin "2") (pinfunction "2_2") (pintype "passive"))
      (node (ref "B12") (pin "2") (pinfunction "2_2") (pintype "passive"))
      (node (ref "B13") (pin "2") (pinfunction "2_2") (pintype "passive"))
      (node (ref "B4") (pin "2") (pinfunction "2_2") (pintype "passive"))
      (node (ref "B8") (pin "2") (pinfunction "2_2") (pintype "passive"))
      (node (ref "C21") (pin "1") (pinfunction "1_1") (pintype "passive"))
      (node (ref "C23") (pin "1") (pinfunction "1_1") (pintype "passive"))
      (node (ref "C24") (pin "1") (pinfunction "1_1") (pintype "passive"))
      (node (ref "C25") (pin "1") (pinfunction "1_1") (pintype "passive"))
      (node (ref "C26") (pin "1") (pinfunction "1_1") (pintype "passive"))
      (node (ref "C27") (pin "1") (pinfunction "1_1") (pintype "passive"))
      (node (ref "C28") (pin "1") (pinfunction "1_1") (pintype "passive"))
      (node (ref "C30") (pin "1") (pinfunction "1_1") (pintype "passive"))
      (node (ref "C31") (pin "1") (pinfunction "1_1") (pintype "passive"))
      (node (ref "C32") (pin "1") (pinfunction "1_1") (pintype "passive"))
      (node (ref "C33") (pin "1") (pinfunction "1_1") (pintype "passive"))
      (node (ref "C36") (pin "1") (pinfunction "1_1") (pintype "passive"))
      (node (ref "C37") (pin "1") (pinfunction "1_1") (pintype "passive"))
      (node (ref "C38") (pin "1") (pinfunction "1_1") (pintype "passive"))
      (node (ref "C39") (pin "1") (pinfunction "1_1") (pintype "passive"))
      (node (ref "C40") (pin "1") (pinfunction "1_1") (pintype "passive"))
      (node (ref "C41") (pin "1") (pinfunction "1_1") (pintype "passive"))
      (node (ref "C42") (pin "2") (pinfunction "2_2") (pintype "passive"))
      (node (ref "C7") (pin "2") (pinfunction "2_2") (pintype "passive"))
      (node (ref "C8") (pin "2") (pinfunction "2_2") (pintype "passive"))
      (node (ref "C9") (pin "2") (pinfunction "2_2") (pintype "passive"))
      (node (ref "DA0") (pin "26") (pinfunction "DCOM_26") (pintype "bidirectional"))
      (node (ref "DA1") (pin "16") (pinfunction "DGND_16") (pintype "bidirectional"))
      (node (ref "DA1_REF") (pin "1") (pinfunction "GND_F_1") (pintype "bidirectional"))
      (node (ref "DA1_REF") (pin "2") (pinfunction "GND_S_2") (pintype "bidirectional"))
      (node (ref "FPGA") (pin "25") (pinfunction "25_25") (pintype "output"))
      (node (ref "IC1") (pin "4") (pinfunction "V-_4") (pintype "power_in"))
      (node (ref "IC3") (pin "2") (pinfunction "GND_2") (pintype "passive"))
      (node (ref "JP1") (pin "3") (pinfunction "3_3") (pintype "passive"))
      (node (ref "JP14") (pin "1") (pinfunction "1_1") (pintype "passive"))
      (node (ref "JP14") (pin "2") (pinfunction "2_2") (pintype "passive"))
      (node (ref "JP4") (pin "2") (pinfunction "2_2") (pintype "passive"))
      (node (ref "JP6") (pin "1") (pinfunction "1_1") (pintype "passive"))
      (node (ref "JP6") (pin "2") (pinfunction "2_2") (pintype "passive"))
      (node (ref "JP8") (pin "2") (pinfunction "2_2") (pintype "passive"))
      (node (ref "P1") (pin "4") (pinfunction "VSS_4") (pintype "bidirectional"))
      (node (ref "P1") (pin "6") (pinfunction "GND_6") (pintype "bidirectional"))
      (node (ref "R11") (pin "1") (pinfunction "1_1") (pintype "passive"))
      (node (ref "R12") (pin "1") (pinfunction "1_1") (pintype "passive"))
      (node (ref "R16") (pin "1") (pinfunction "1_1") (pintype "passive"))
      (node (ref "R2") (pin "2") (pinfunction "2_2") (pintype "passive"))
      (node (ref "R28") (pin "2") (pinfunction "2_2") (pintype "passive"))
      (node (ref "R31") (pin "2") (pinfunction "2_2") (pintype "passive"))
      (node (ref "SENSOR") (pin "11") (pinfunction "GND_11") (pintype "bidirectional"))
      (node (ref "SENSOR") (pin "3") (pinfunction "A0_3") (pintype "bidirectional"))
      (node (ref "SENSOR") (pin "4") (pinfunction "A1_4") (pintype "bidirectional"))
    )
    (net (code "50") (name "GNDINT") (class "Default")
      (node (ref "B1") (pin "1") (pinfunction "1_1") (pintype "passive"))
      (node (ref "B6") (pin "1") (pinfunction "1_1") (pintype "passive"))
      (node (ref "C10") (pin "1") (pinfunction "1_1") (pintype "passive"))
      (node (ref "C11") (pin "1") (pinfunction "1_1") (pintype "passive"))
      (node (ref "C13") (pin "1") (pinfunction "1_1") (pintype "passive"))
      (node (ref "C43") (pin "1") (pinfunction "1_1") (pintype "passive"))
      (node (ref "C44") (pin "2") (pinfunction "2_2") (pintype "passive"))
      (node (ref "C5") (pin "1") (pinfunction "1_1") (pintype "passive"))
      (node (ref "C6") (pin "1") (pinfunction "1_1") (pintype "passive"))
      (node (ref "DA0") (pin "16") (pinfunction "REFLO_16") (pintype "bidirectional"))
      (node (ref "DA0") (pin "20") (pinfunction "ACOM_20") (pintype "bidirectional"))
      (node (ref "P1") (pin "2") (pinfunction "A_2") (pintype "bidirectional"))
      (node (ref "R25") (pin "2") (pinfunction "2_2") (pintype "passive"))
      (node (ref "T1") (pin "P$2") (pinfunction "2_P$2") (pintype "bidirectional"))
      (node (ref "U$5") (pin "3") (pinfunction "P$3_3") (pintype "passive"))
    )
    (net (code "51") (name "Net-(ADC-SCLK)") (class "Default")
      (node (ref "ADC") (pin "4") (pinfunction "SCLK_4") (pintype "bidirectional"))
      (node (ref "C42") (pin "1") (pinfunction "1_1") (pintype "passive"))
      (node (ref "R32") (pin "2") (pinfunction "2_2") (pintype "passive"))
    )
    (net (code "52") (name "Net-(ADC-VDD)") (class "Default")
      (node (ref "ADC") (pin "1") (pinfunction "VDD_1") (pintype "bidirectional"))
      (node (ref "C21") (pin "2") (pinfunction "2_2") (pintype "passive"))
      (node (ref "C23") (pin "2") (pinfunction "2_2") (pintype "passive"))
      (node (ref "C24") (pin "2") (pinfunction "2_2") (pintype "passive"))
      (node (ref "JP7") (pin "2") (pinfunction "2_2") (pintype "passive"))
    )
    (net (code "53") (name "Net-(ADC-VIN)") (class "Default")
      (node (ref "ADC") (pin "3") (pinfunction "VIN_3") (pintype "bidirectional"))
      (node (ref "C29") (pin "2") (pinfunction "2_2") (pintype "passive"))
      (node (ref "IC1") (pin "1") (pinfunction "OUT_1") (pintype "output"))
      (node (ref "R16") (pin "2") (pinfunction "2_2") (pintype "passive"))
      (node (ref "U$7") (pin "2") (pinfunction "P$2_2") (pintype "bidirectional"))
      (node (ref "V_PREAMP") (pin "1") (pinfunction "P_1") (pintype "passive"))
    )
    (net (code "54") (name "Net-(B1-Pad2)") (class "Default")
      (node (ref "B1") (pin "2") (pinfunction "2_2") (pintype "passive"))
      (node (ref "JP3") (pin "1") (pinfunction "1_1") (pintype "passive"))
    )
    (net (code "55") (name "Net-(B2-Pad1)") (class "Default")
      (node (ref "B2") (pin "1") (pinfunction "1_1") (pintype "passive"))
      (node (ref "JP3") (pin "2") (pinfunction "2_2") (pintype "passive"))
    )
    (net (code "56") (name "Net-(B3-Pad2)") (class "Default")
      (node (ref "B3") (pin "2") (pinfunction "2_2") (pintype "passive"))
      (node (ref "JP1") (pin "1") (pinfunction "1_1") (pintype "passive"))
    )
    (net (code "57") (name "Net-(B4-Pad1)") (class "Default")
      (node (ref "B4") (pin "1") (pinfunction "1_1") (pintype "passive"))
      (node (ref "JP1") (pin "2") (pinfunction "2_2") (pintype "passive"))
    )
    (net (code "58") (name "Net-(B5-Pad2)") (class "Default")
      (node (ref "B5") (pin "2") (pinfunction "2_2") (pintype "passive"))
      (node (ref "FPGA") (pin "24") (pinfunction "24_24") (pintype "output"))
    )
    (net (code "59") (name "Net-(C1-Pad1)") (class "Default")
      (node (ref "C1") (pin "1") (pinfunction "1_1") (pintype "passive"))
      (node (ref "L3") (pin "1") (pinfunction "1_1") (pintype "passive"))
    )
    (net (code "60") (name "Net-(C2-Pad1)") (class "Default")
      (node (ref "C2") (pin "1") (pinfunction "1_1") (pintype "passive"))
      (node (ref "L2") (pin "2") (pinfunction "2_2") (pintype "passive"))
      (node (ref "LOPT") (pin "2") (pinfunction "2_2") (pintype "passive"))
    )
    (net (code "61") (name "Net-(C15-Pad2)") (class "Default")
      (node (ref "C15") (pin "2") (pinfunction "2_2") (pintype "passive"))
      (node (ref "R4") (pin "2") (pinfunction "2_2") (pintype "passive"))
    )
    (net (code "62") (name "Net-(C20-Pad1)") (class "Default")
      (node (ref "C20") (pin "1") (pinfunction "1_1") (pintype "passive"))
      (node (ref "R13") (pin "2") (pinfunction "2_2") (pintype "passive"))
    )
    (net (code "63") (name "Net-(C22-Pad2)") (class "Default")
      (node (ref "C22") (pin "2") (pinfunction "2_2") (pintype "passive"))
      (node (ref "R17") (pin "2") (pinfunction "2_2") (pintype "passive"))
    )
    (net (code "64") (name "Net-(DA0-SLEEP)") (class "Default")
      (node (ref "DA0") (pin "15") (pinfunction "SLEEP_15") (pintype "bidirectional"))
      (node (ref "R25") (pin "1") (pinfunction "1_1") (pintype "passive"))
    )
    (net (code "65") (name "Net-(FPGA-Pad7)") (class "Default")
      (node (ref "FPGA") (pin "7") (pinfunction "7_7") (pintype "bidirectional"))
      (node (ref "JP13") (pin "1") (pinfunction "1_1") (pintype "passive"))
    )
    (net (code "66") (name "Net-(FPGA-Pad8)") (class "Default")
      (node (ref "FPGA") (pin "8") (pinfunction "8_8") (pintype "bidirectional"))
      (node (ref "JP13") (pin "2") (pinfunction "2_2") (pintype "passive"))
    )
    (net (code "67") (name "Net-(FPGA-Pad9)") (class "Default")
      (node (ref "FPGA") (pin "9") (pinfunction "9_9") (pintype "output"))
      (node (ref "JP11") (pin "1") (pinfunction "1_1") (pintype "passive"))
    )
    (net (code "68") (name "Net-(FPGA-Pad10)") (class "Default")
      (node (ref "FPGA") (pin "10") (pinfunction "10_10") (pintype "output"))
      (node (ref "JP11") (pin "2") (pinfunction "2_2") (pintype "passive"))
    )
    (net (code "69") (name "Net-(FPGA-Pad11)") (class "Default")
      (node (ref "FPGA") (pin "11") (pinfunction "11_11") (pintype "output"))
      (node (ref "JP11") (pin "3") (pinfunction "3_3") (pintype "passive"))
    )
    (net (code "70") (name "Net-(FPGA-Pad12)") (class "Default")
      (node (ref "FPGA") (pin "12") (pinfunction "12_12") (pintype "output"))
      (node (ref "JP11") (pin "4") (pinfunction "4_4") (pintype "passive"))
    )
    (net (code "71") (name "Net-(FPGA-Pad13)") (class "Default")
      (node (ref "FPGA") (pin "13") (pinfunction "13_13") (pintype "output"))
      (node (ref "JP10") (pin "4") (pinfunction "4_4") (pintype "passive"))
    )
    (net (code "72") (name "Net-(FPGA-Pad14)") (class "Default")
      (node (ref "FPGA") (pin "14") (pinfunction "14_14") (pintype "output"))
      (node (ref "JP10") (pin "3") (pinfunction "3_3") (pintype "passive"))
    )
    (net (code "73") (name "Net-(FPGA-Pad15)") (class "Default")
      (node (ref "FPGA") (pin "15") (pinfunction "15_15") (pintype "output"))
      (node (ref "JP10") (pin "2") (pinfunction "2_2") (pintype "passive"))
    )
    (net (code "74") (name "Net-(FPGA-Pad16)") (class "Default")
      (node (ref "FPGA") (pin "16") (pinfunction "16_16") (pintype "output"))
      (node (ref "JP10") (pin "1") (pinfunction "1_1") (pintype "passive"))
    )
    (net (code "75") (name "Net-(FPGA-Pad17)") (class "Default")
      (node (ref "FPGA") (pin "17") (pinfunction "17_17") (pintype "output"))
      (node (ref "JP12") (pin "1") (pinfunction "1_1") (pintype "passive"))
    )
    (net (code "76") (name "Net-(FPGA-Pad18)") (class "Default")
      (node (ref "FPGA") (pin "18") (pinfunction "18_18") (pintype "output"))
      (node (ref "JP12") (pin "2") (pinfunction "2_2") (pintype "passive"))
    )
    (net (code "77") (name "Net-(FPGA-Pad19)") (class "Default")
      (node (ref "FPGA") (pin "19") (pinfunction "19_19") (pintype "output"))
      (node (ref "JP12") (pin "3") (pinfunction "3_3") (pintype "passive"))
    )
    (net (code "78") (name "Net-(FPGA-Pad20)") (class "Default")
      (node (ref "FPGA") (pin "20") (pinfunction "20_20") (pintype "output"))
      (node (ref "JP9") (pin "4") (pinfunction "4_4") (pintype "passive"))
    )
    (net (code "79") (name "Net-(FPGA-Pad21)") (class "Default")
      (node (ref "FPGA") (pin "21") (pinfunction "21_21") (pintype "output"))
      (node (ref "JP9") (pin "3") (pinfunction "3_3") (pintype "passive"))
    )
    (net (code "80") (name "Net-(FPGA-Pad22)") (class "Default")
      (node (ref "FPGA") (pin "22") (pinfunction "22_22") (pintype "output"))
      (node (ref "JP9") (pin "2") (pinfunction "2_2") (pintype "passive"))
    )
    (net (code "81") (name "Net-(FPGA-Pad23)") (class "Default")
      (node (ref "FPGA") (pin "23") (pinfunction "23_23") (pintype "output"))
      (node (ref "JP9") (pin "1") (pinfunction "1_1") (pintype "passive"))
    )
    (net (code "82") (name "Net-(IC1A-+IN)") (class "Default")
      (node (ref "IC1") (pin "3") (pinfunction "+IN_3") (pintype "input"))
      (node (ref "R13") (pin "1") (pinfunction "1_1") (pintype "passive"))
      (node (ref "R14") (pin "1") (pinfunction "1_1") (pintype "passive"))
      (node (ref "R17") (pin "1") (pinfunction "1_1") (pintype "passive"))
    )
    (net (code "83") (name "Net-(IC1A--IN)") (class "Default")
      (node (ref "C29") (pin "1") (pinfunction "1_1") (pintype "passive"))
      (node (ref "IC1") (pin "2") (pinfunction "-IN_2") (pintype "input"))
      (node (ref "R15") (pin "2") (pinfunction "2_2") (pintype "passive"))
      (node (ref "U$7") (pin "1") (pinfunction "P$1_1") (pintype "bidirectional"))
    )
    (net (code "84") (name "Net-(IC1B-+IN)") (class "Default")
      (node (ref "IC1") (pin "5") (pinfunction "+IN_5") (pintype "input"))
      (node (ref "R10") (pin "1") (pinfunction "1_1") (pintype "passive"))
      (node (ref "R11") (pin "2") (pinfunction "2_2") (pintype "passive"))
    )
    (net (code "85") (name "Net-(IC2-VI)") (class "Default")
      (node (ref "C45") (pin "1") (pinfunction "1_1") (pintype "passive"))
      (node (ref "IC2") (pin "1") (pinfunction "VI_1") (pintype "input"))
      (node (ref "JP2") (pin "2") (pinfunction "2_2") (pintype "passive"))
    )
    (net (code "86") (name "Net-(IC3-VI)") (class "Default")
      (node (ref "C36") (pin "2") (pinfunction "2_2") (pintype "passive"))
      (node (ref "IC3") (pin "1") (pinfunction "VI_1") (pintype "input"))
      (node (ref "JP4") (pin "1") (pinfunction "1_1") (pintype "passive"))
    )
    (net (code "87") (name "Net-(JACK-P$2)") (class "Default")
      (node (ref "C20") (pin "2") (pinfunction "2_2") (pintype "passive"))
      (node (ref "JACK") (pin "2") (pinfunction "P$2_2") (pintype "bidirectional"))
    )
    (net (code "88") (name "Net-(JACK-P$3)") (class "Default")
      (node (ref "C22") (pin "1") (pinfunction "1_1") (pintype "passive"))
      (node (ref "JACK") (pin "3") (pinfunction "P$3_3") (pintype "bidirectional"))
    )
    (net (code "89") (name "Net-(JP5-Pad1)") (class "Default")
      (node (ref "JP5") (pin "1") (pinfunction "1_1") (pintype "passive"))
      (node (ref "R30") (pin "2") (pinfunction "2_2") (pintype "passive"))
    )
    (net (code "90") (name "Net-(JP5-Pad2)") (class "Default")
      (node (ref "JP5") (pin "2") (pinfunction "2_2") (pintype "passive"))
      (node (ref "R29") (pin "1") (pinfunction "1_1") (pintype "passive"))
      (node (ref "R31") (pin "1") (pinfunction "1_1") (pintype "passive"))
    )
    (net (code "91") (name "Net-(JP7-Pad3)") (class "Default")
      (node (ref "JP7") (pin "3") (pinfunction "3_3") (pintype "passive"))
      (node (ref "JP8") (pin "1") (pinfunction "1_1") (pintype "passive"))
    )
    (net (code "92") (name "Net-(L1-Pad2)") (class "Default")
      (node (ref "L1") (pin "2") (pinfunction "2_2") (pintype "passive"))
      (node (ref "L2") (pin "1") (pinfunction "1_1") (pintype "passive"))
      (node (ref "L3") (pin "2") (pinfunction "2_2") (pintype "passive"))
    )
    (net (code "93") (name "Net-(P1-EC)") (class "Default")
      (node (ref "C28") (pin "2") (pinfunction "2_2") (pintype "passive"))
      (node (ref "P1") (pin "5") (pinfunction "EC_5") (pintype "bidirectional"))
    )
    (net (code "94") (name "Net-(R4-Pad1)") (class "Default")
      (node (ref "R4") (pin "1") (pinfunction "1_1") (pintype "passive"))
      (node (ref "R5") (pin "1") (pinfunction "1_1") (pintype "passive"))
      (node (ref "R6") (pin "1") (pinfunction "1_1") (pintype "passive"))
    )
    (net (code "95") (name "Net-(SENSOR-CT)") (class "Default")
      (node (ref "R19") (pin "1") (pinfunction "1_1") (pintype "passive"))
      (node (ref "SENSOR") (pin "10") (pinfunction "CT_10") (pintype "bidirectional"))
    )
    (net (code "96") (name "Net-(U$2-BIAS)") (class "Default")
      (node (ref "R1") (pin "1") (pinfunction "1_1") (pintype "passive"))
      (node (ref "U$2") (pin "6") (pinfunction "BIAS_6") (pintype "bidirectional"))
    )
    (net (code "97") (name "Net-(U$2-IN)") (class "Default")
      (node (ref "C2") (pin "2") (pinfunction "2_2") (pintype "passive"))
      (node (ref "U$2") (pin "1") (pinfunction "IN_1") (pintype "bidirectional"))
    )
    (net (code "98") (name "Net-(U$2-L)") (class "Default")
      (node (ref "L4") (pin "2") (pinfunction "2_2") (pintype "passive"))
      (node (ref "U$2") (pin "4") (pinfunction "L_4") (pintype "bidirectional"))
    )
    (net (code "99") (name "Net-(U$2-OUT)") (class "Default")
      (node (ref "C3") (pin "1") (pinfunction "1_1") (pintype "passive"))
      (node (ref "U$2") (pin "5") (pinfunction "OUT_5") (pintype "bidirectional"))
    )
    (net (code "100") (name "Net-(U$3-IN)") (class "Default")
      (node (ref "R6") (pin "2") (pinfunction "2_2") (pintype "passive"))
      (node (ref "U$3") (pin "3") (pinfunction "IN_3") (pintype "bidirectional"))
    )
    (net (code "101") (name "Net-(U$3-OUT)") (class "Default")
      (node (ref "C14") (pin "2") (pinfunction "2_2") (pintype "passive"))
      (node (ref "C19") (pin "1") (pinfunction "1_1") (pintype "passive"))
      (node (ref "R3") (pin "1") (pinfunction "1_1") (pintype "passive"))
      (node (ref "U$3") (pin "1") (pinfunction "OUT_1") (pintype "bidirectional"))
    )
    (net (code "102") (name "Net-(U$4-IND)") (class "Default")
      (node (ref "L7") (pin "2") (pinfunction "2_2") (pintype "passive"))
      (node (ref "U$4") (pin "1") (pinfunction "IND_1") (pintype "bidirectional"))
    )
    (net (code "103") (name "Net-(U$4-OUT+)") (class "Default")
      (node (ref "C15") (pin "1") (pinfunction "1_1") (pintype "passive"))
      (node (ref "R8") (pin "2") (pinfunction "2_2") (pintype "passive"))
      (node (ref "U$4") (pin "6") (pinfunction "OUT+_6") (pintype "bidirectional"))
    )
    (net (code "104") (name "Net-(U$4-OUT-)") (class "Default")
      (node (ref "R7") (pin "1") (pinfunction "1_1") (pintype "passive"))
      (node (ref "U$4") (pin "4") (pinfunction "OUT-_4") (pintype "bidirectional"))
    )
    (net (code "105") (name "Net-(U$6-IF)") (class "Default")
      (node (ref "C3") (pin "2") (pinfunction "2_2") (pintype "passive"))
      (node (ref "U$6") (pin "P$2") (pinfunction "IF_P$2") (pintype "bidirectional"))
    )
    (net (code "106") (name "Net-(U$6-LO)") (class "Default")
      (node (ref "C19") (pin "2") (pinfunction "2_2") (pintype "passive"))
      (node (ref "U$6") (pin "P$6") (pinfunction "LO_P$6") (pintype "bidirectional"))
    )
    (net (code "107") (name "Net-(U$6-RF)") (class "Default")
      (node (ref "U$6") (pin "P$3") (pinfunction "RF_P$3") (pintype "bidirectional"))
      (node (ref "X1") (pin "1") (pinfunction "1_1") (pintype "passive"))
    )
    (net (code "108") (name "unconnected-(DA0-NC_1-Pad14)") (class "Default")
      (node (ref "DA0") (pin "14") (pinfunction "NC_1_14") (pintype "bidirectional"))
    )
    (net (code "109") (name "unconnected-(DA0-NC_2-Pad13)") (class "Default")
      (node (ref "DA0") (pin "13") (pinfunction "NC_2_13") (pintype "bidirectional"))
    )
    (net (code "110") (name "unconnected-(DA0-NC_3-Pad12)") (class "Default")
      (node (ref "DA0") (pin "12") (pinfunction "NC_3_12") (pintype "bidirectional"))
    )
    (net (code "111") (name "unconnected-(DA0-NC_4-Pad11)") (class "Default")
      (node (ref "DA0") (pin "11") (pinfunction "NC_4_11") (pintype "bidirectional"))
    )
    (net (code "112") (name "unconnected-(DA1-NC-Pad9)") (class "Default")
      (node (ref "DA1") (pin "9") (pinfunction "NC_9") (pintype "bidirectional"))
    )
    (net (code "113") (name "unconnected-(T1-NC-PadP$5)") (class "Default")
      (node (ref "T1") (pin "P$5") (pinfunction "NC_P$5") (pintype "bidirectional"))
    )
    (net (code "114") (name "unconnected-(U$5-P$1-Pad1)") (class "Default")
      (node (ref "U$5") (pin "1") (pinfunction "P$1_1") (pintype "bidirectional"))
    )
    (net (code "115") (name "unconnected-(U$7-P$3-Pad3)") (class "Default")
      (node (ref "U$7") (pin "3") (pinfunction "P$3_3") (pintype "passive"))
    )
  )
)
